# regsimple2addfp.net
KiCad netlist of a schematic drawn in EAGLE
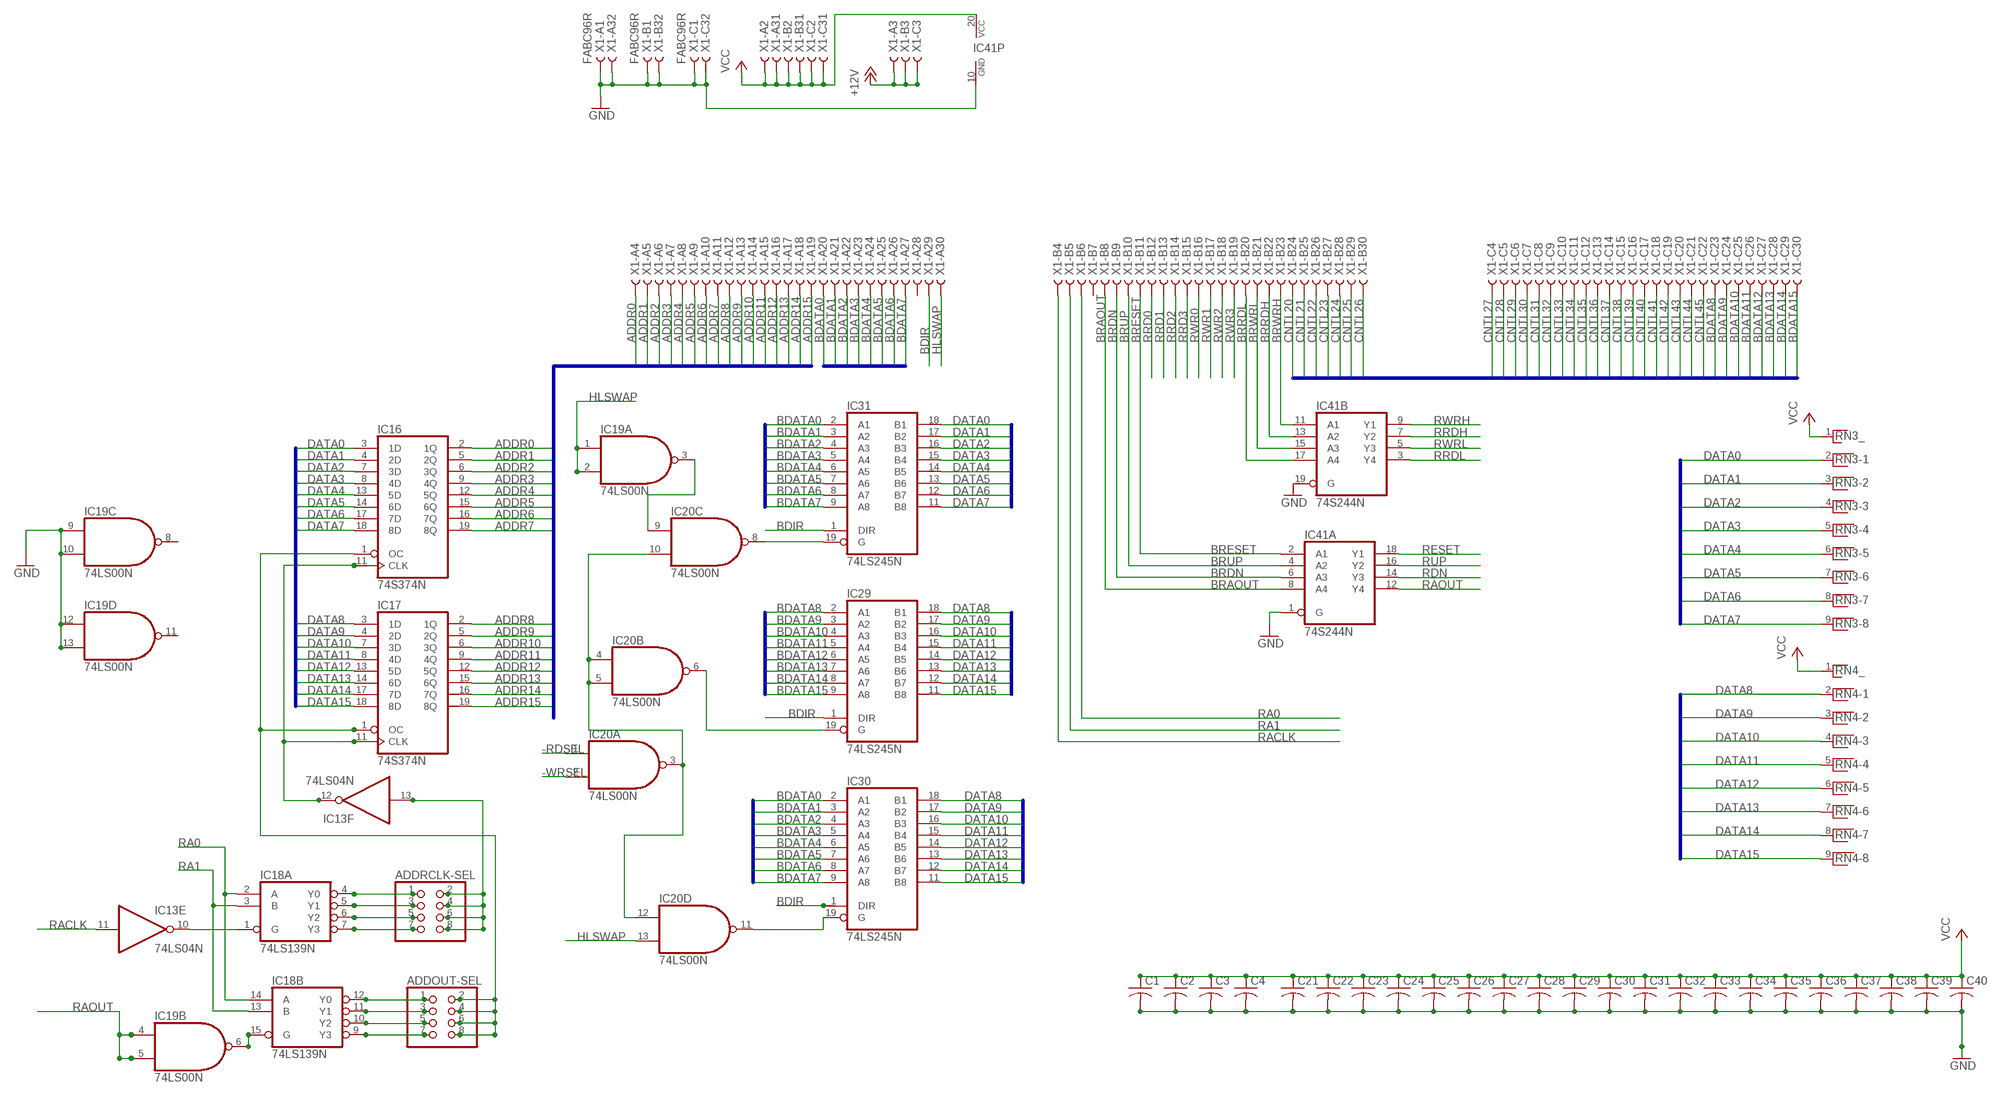
[diagram p0: schematic, sheet 1]
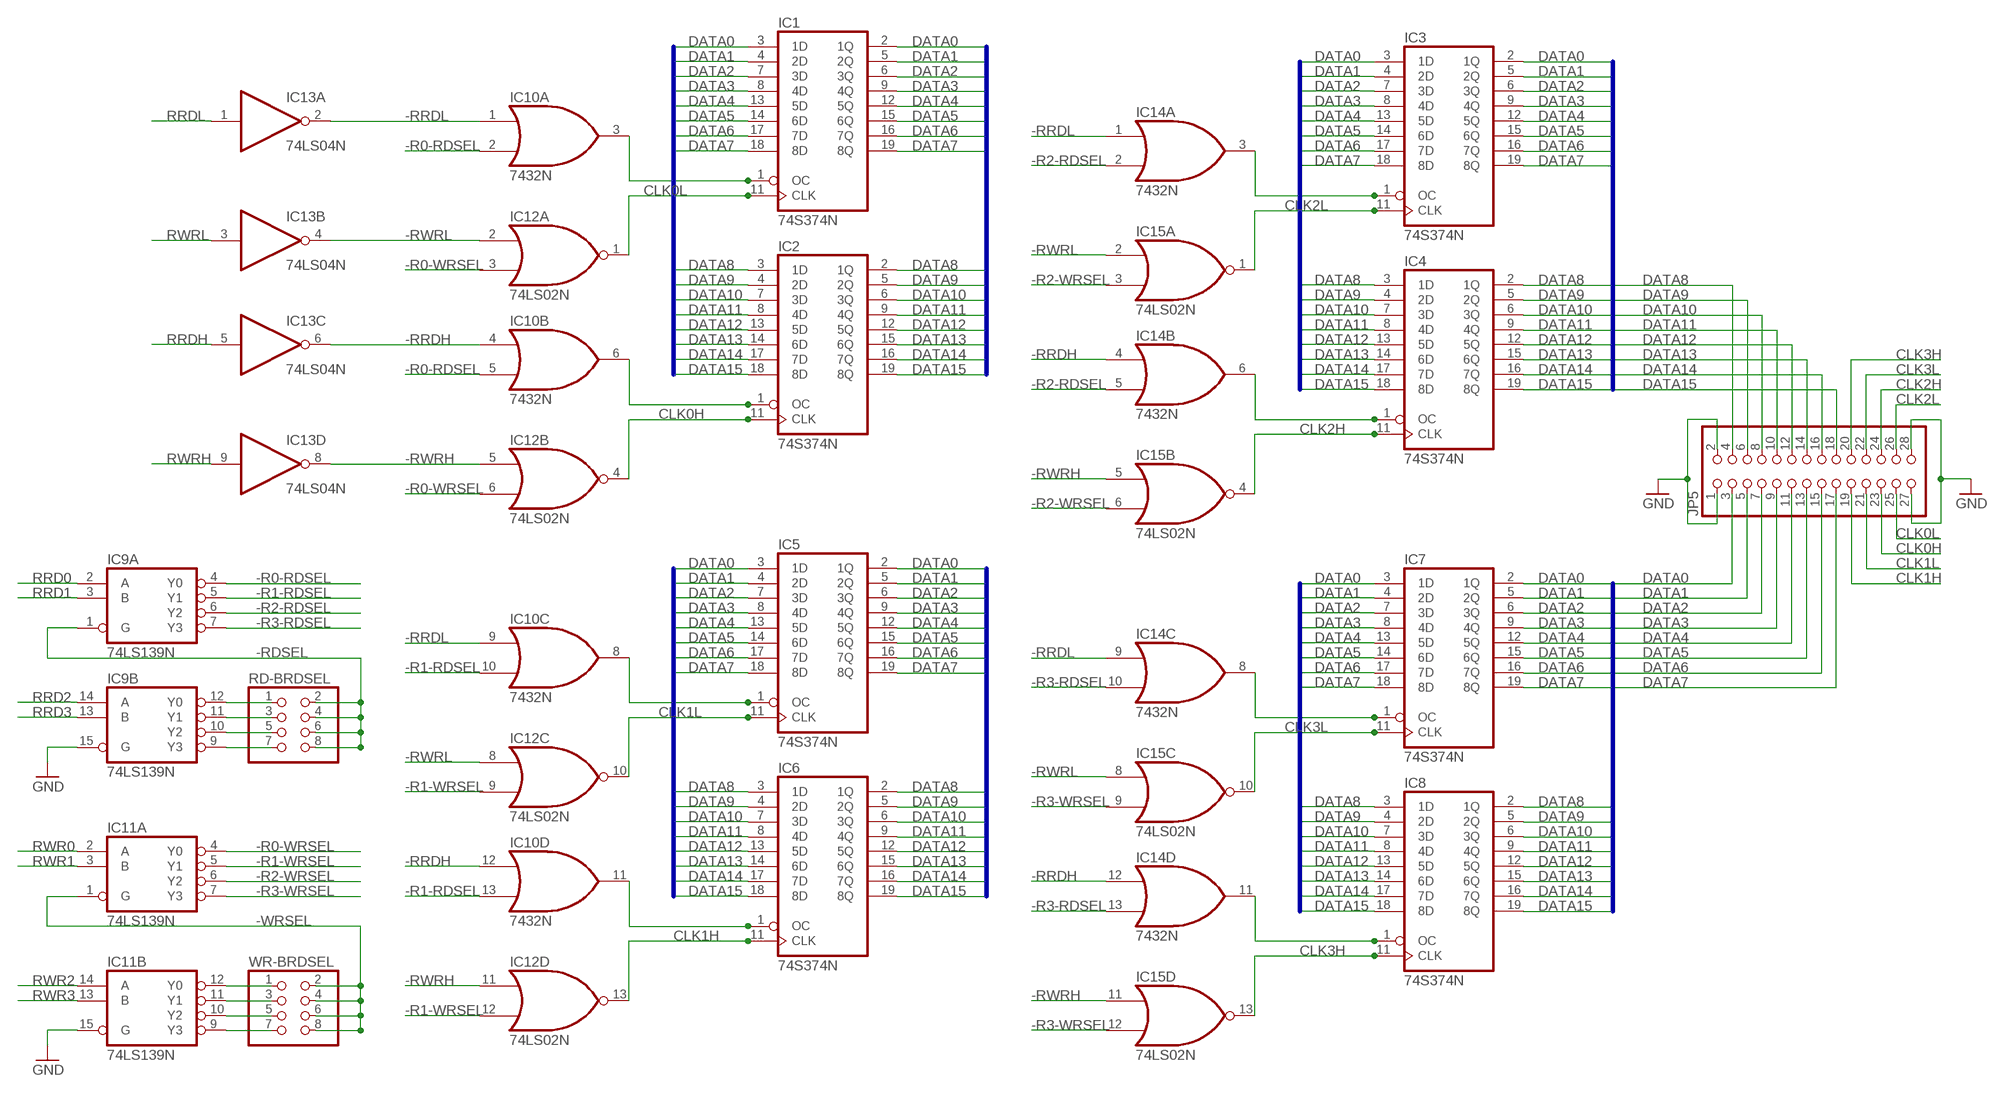
[diagram p1: schematic, sheet 2]

(export (version "E")
  (design (tool "Eeschema 10.0.6"))
  (components
    (comp (ref "IC1")
      (value "74S374N")
      (footprint "eagle-import:DIL20")
      (libsource (lib "eagle-import") (part "74374NS"))
    )
    (comp (ref "IC2")
      (value "74S374N")
      (footprint "eagle-import:DIL20")
      (libsource (lib "eagle-import") (part "74374NS"))
    )
    (comp (ref "IC3")
      (value "74S374N")
      (footprint "eagle-import:DIL20")
      (libsource (lib "eagle-import") (part "74374NS"))
    )
    (comp (ref "IC4")
      (value "74S374N")
      (footprint "eagle-import:DIL20")
      (libsource (lib "eagle-import") (part "74374NS"))
    )
    (comp (ref "IC5")
      (value "74S374N")
      (footprint "eagle-import:DIL20")
      (libsource (lib "eagle-import") (part "74374NS"))
    )
    (comp (ref "IC6")
      (value "74S374N")
      (footprint "eagle-import:DIL20")
      (libsource (lib "eagle-import") (part "74374NS"))
    )
    (comp (ref "IC7")
      (value "74S374N")
      (footprint "eagle-import:DIL20")
      (libsource (lib "eagle-import") (part "74374NS"))
    )
    (comp (ref "IC8")
      (value "74S374N")
      (footprint "eagle-import:DIL20")
      (libsource (lib "eagle-import") (part "74374NS"))
    )
    (comp (ref "IC9")
      (value "74LS139N")
      (footprint "eagle-import:DIL16")
      (libsource (lib "eagle-import") (part "74139NLS"))
    )
    (comp (ref "IC10")
      (value "7432N")
      (footprint "eagle-import:DIL14")
      (libsource (lib "eagle-import") (part "7432N"))
    )
    (comp (ref "IC11")
      (value "74LS139N")
      (footprint "eagle-import:DIL16")
      (libsource (lib "eagle-import") (part "74139NLS"))
    )
    (comp (ref "IC12")
      (value "74LS02N")
      (footprint "eagle-import:DIL14")
      (libsource (lib "eagle-import") (part "7402NLS"))
    )
    (comp (ref "IC13")
      (value "74LS04N")
      (footprint "eagle-import:DIL14")
      (libsource (lib "eagle-import") (part "7404NLS"))
    )
    (comp (ref "IC14")
      (value "7432N")
      (footprint "eagle-import:DIL14")
      (libsource (lib "eagle-import") (part "7432N"))
    )
    (comp (ref "IC15")
      (value "74LS02N")
      (footprint "eagle-import:DIL14")
      (libsource (lib "eagle-import") (part "7402NLS"))
    )
    (comp (ref "JP5")
      (value "PINHD-2X14")
      (footprint "eagle-import:2X14")
      (libsource (lib "eagle-import") (part "PINHD-2X14"))
    )
    (comp (ref "RD-BRDSEL")
      (value "PINHD-2X4")
      (footprint "eagle-import:2X04")
      (libsource (lib "eagle-import") (part "PINHD-2X4"))
    )
    (comp (ref "WR-BRDSEL")
      (value "PINHD-2X4")
      (footprint "eagle-import:2X04")
      (libsource (lib "eagle-import") (part "PINHD-2X4"))
    )
    (comp (ref "ADDOUT-SEL")
      (value "PINHD-2X4")
      (footprint "eagle-import:2X04")
      (libsource (lib "eagle-import") (part "PINHD-2X4"))
    )
    (comp (ref "ADDRCLK-SEL")
      (value "PINHD-2X4")
      (footprint "eagle-import:2X04")
      (libsource (lib "eagle-import") (part "PINHD-2X4"))
    )
    (comp (ref "C1")
      (value "C-US025-040X050")
      (footprint "eagle-import:C025-040X050")
      (libsource (lib "eagle-import") (part "C-US025-040X050"))
    )
    (comp (ref "C2")
      (value "C-US025-040X050")
      (footprint "eagle-import:C025-040X050")
      (libsource (lib "eagle-import") (part "C-US025-040X050"))
    )
    (comp (ref "C3")
      (value "C-US025-040X050")
      (footprint "eagle-import:C025-040X050")
      (libsource (lib "eagle-import") (part "C-US025-040X050"))
    )
    (comp (ref "C4")
      (value "C-US025-040X050")
      (footprint "eagle-import:C025-040X050")
      (libsource (lib "eagle-import") (part "C-US025-040X050"))
    )
    (comp (ref "C21")
      (value "C-US025-040X050")
      (footprint "eagle-import:C025-040X050")
      (libsource (lib "eagle-import") (part "C-US025-040X050"))
    )
    (comp (ref "C22")
      (value "C-US025-040X050")
      (footprint "eagle-import:C025-040X050")
      (libsource (lib "eagle-import") (part "C-US025-040X050"))
    )
    (comp (ref "C23")
      (value "C-US025-040X050")
      (footprint "eagle-import:C025-040X050")
      (libsource (lib "eagle-import") (part "C-US025-040X050"))
    )
    (comp (ref "C24")
      (value "C-US025-040X050")
      (footprint "eagle-import:C025-040X050")
      (libsource (lib "eagle-import") (part "C-US025-040X050"))
    )
    (comp (ref "C25")
      (value "C-US025-040X050")
      (footprint "eagle-import:C025-040X050")
      (libsource (lib "eagle-import") (part "C-US025-040X050"))
    )
    (comp (ref "C26")
      (value "C-US025-040X050")
      (footprint "eagle-import:C025-040X050")
      (libsource (lib "eagle-import") (part "C-US025-040X050"))
    )
    (comp (ref "C27")
      (value "C-US025-040X050")
      (footprint "eagle-import:C025-040X050")
      (libsource (lib "eagle-import") (part "C-US025-040X050"))
    )
    (comp (ref "C28")
      (value "C-US025-040X050")
      (footprint "eagle-import:C025-040X050")
      (libsource (lib "eagle-import") (part "C-US025-040X050"))
    )
    (comp (ref "C29")
      (value "C-US025-040X050")
      (footprint "eagle-import:C025-040X050")
      (libsource (lib "eagle-import") (part "C-US025-040X050"))
    )
    (comp (ref "C30")
      (value "C-US025-040X050")
      (footprint "eagle-import:C025-040X050")
      (libsource (lib "eagle-import") (part "C-US025-040X050"))
    )
    (comp (ref "C31")
      (value "C-US025-040X050")
      (footprint "eagle-import:C025-040X050")
      (libsource (lib "eagle-import") (part "C-US025-040X050"))
    )
    (comp (ref "C32")
      (value "C-US025-040X050")
      (footprint "eagle-import:C025-040X050")
      (libsource (lib "eagle-import") (part "C-US025-040X050"))
    )
    (comp (ref "C33")
      (value "C-US025-040X050")
      (footprint "eagle-import:C025-040X050")
      (libsource (lib "eagle-import") (part "C-US025-040X050"))
    )
    (comp (ref "C34")
      (value "C-US025-040X050")
      (footprint "eagle-import:C025-040X050")
      (libsource (lib "eagle-import") (part "C-US025-040X050"))
    )
    (comp (ref "C35")
      (value "C-US025-040X050")
      (footprint "eagle-import:C025-040X050")
      (libsource (lib "eagle-import") (part "C-US025-040X050"))
    )
    (comp (ref "C36")
      (value "C-US025-040X050")
      (footprint "eagle-import:C025-040X050")
      (libsource (lib "eagle-import") (part "C-US025-040X050"))
    )
    (comp (ref "C37")
      (value "C-US025-040X050")
      (footprint "eagle-import:C025-040X050")
      (libsource (lib "eagle-import") (part "C-US025-040X050"))
    )
    (comp (ref "C38")
      (value "C-US025-040X050")
      (footprint "eagle-import:C025-040X050")
      (libsource (lib "eagle-import") (part "C-US025-040X050"))
    )
    (comp (ref "C39")
      (value "C-US025-040X050")
      (footprint "eagle-import:C025-040X050")
      (libsource (lib "eagle-import") (part "C-US025-040X050"))
    )
    (comp (ref "C40")
      (value "C-US025-040X050")
      (footprint "eagle-import:C025-040X050")
      (libsource (lib "eagle-import") (part "C-US025-040X050"))
    )
    (comp (ref "IC16")
      (value "74S374N")
      (footprint "eagle-import:DIL20")
      (libsource (lib "eagle-import") (part "74374NS"))
    )
    (comp (ref "IC17")
      (value "74S374N")
      (footprint "eagle-import:DIL20")
      (libsource (lib "eagle-import") (part "74374NS"))
    )
    (comp (ref "IC18")
      (value "74LS139N")
      (footprint "eagle-import:DIL16")
      (libsource (lib "eagle-import") (part "74139NLS"))
    )
    (comp (ref "IC19")
      (value "74LS00N")
      (footprint "eagle-import:DIL14")
      (libsource (lib "eagle-import") (part "7400NLS"))
    )
    (comp (ref "IC20")
      (value "74LS00N")
      (footprint "eagle-import:DIL14")
      (libsource (lib "eagle-import") (part "7400NLS"))
    )
    (comp (ref "IC29")
      (value "74LS245N")
      (footprint "eagle-import:DIL20")
      (libsource (lib "eagle-import") (part "74245NLS"))
    )
    (comp (ref "IC30")
      (value "74LS245N")
      (footprint "eagle-import:DIL20")
      (libsource (lib "eagle-import") (part "74245NLS"))
    )
    (comp (ref "IC31")
      (value "74LS245N")
      (footprint "eagle-import:DIL20")
      (libsource (lib "eagle-import") (part "74245NLS"))
    )
    (comp (ref "IC41")
      (value "74S244N")
      (footprint "eagle-import:DIL20")
      (libsource (lib "eagle-import") (part "74244NS"))
    )
    (comp (ref "RN3")
      (value "RNX8")
      (footprint "eagle-import:RN-9")
      (libsource (lib "eagle-import") (part "RNX8"))
    )
    (comp (ref "RN4")
      (value "RNX8")
      (footprint "eagle-import:RN-9")
      (libsource (lib "eagle-import") (part "RNX8"))
    )
    (comp (ref "X1")
      (value "FABC96R")
      (footprint "eagle-import:FABC96R")
      (libsource (lib "eagle-import") (part "FABC96R"))
    )
  )
  (nets
    (net (code "1") (name "+12V") (class "Default")
      (node (ref "X1") (pin "A3") (pinfunction "B_A3") (pintype "passive"))
      (node (ref "X1") (pin "B3") (pinfunction "B_B3") (pintype "passive"))
      (node (ref "X1") (pin "C3") (pinfunction "B_C3") (pintype "passive"))
    )
    (net (code "2") (name "-R0-RDSEL") (class "Default")
      (node (ref "IC10") (pin "2") (pinfunction "I1_2") (pintype "input"))
      (node (ref "IC10") (pin "5") (pinfunction "I1_5") (pintype "input"))
      (node (ref "IC9") (pin "4") (pinfunction "Y0_4") (pintype "output"))
    )
    (net (code "3") (name "-R0-WRSEL") (class "Default")
      (node (ref "IC11") (pin "4") (pinfunction "Y0_4") (pintype "output"))
      (node (ref "IC12") (pin "3") (pinfunction "I1_3") (pintype "input"))
      (node (ref "IC12") (pin "6") (pinfunction "I1_6") (pintype "input"))
    )
    (net (code "4") (name "-R1-RDSEL") (class "Default")
      (node (ref "IC10") (pin "10") (pinfunction "I1_10") (pintype "input"))
      (node (ref "IC10") (pin "13") (pinfunction "I1_13") (pintype "input"))
      (node (ref "IC9") (pin "5") (pinfunction "Y1_5") (pintype "output"))
    )
    (net (code "5") (name "-R1-WRSEL") (class "Default")
      (node (ref "IC11") (pin "5") (pinfunction "Y1_5") (pintype "output"))
      (node (ref "IC12") (pin "12") (pinfunction "I1_12") (pintype "input"))
      (node (ref "IC12") (pin "9") (pinfunction "I1_9") (pintype "input"))
    )
    (net (code "6") (name "-R2-RDSEL") (class "Default")
      (node (ref "IC14") (pin "2") (pinfunction "I1_2") (pintype "input"))
      (node (ref "IC14") (pin "5") (pinfunction "I1_5") (pintype "input"))
      (node (ref "IC9") (pin "6") (pinfunction "Y2_6") (pintype "output"))
    )
    (net (code "7") (name "-R2-WRSEL") (class "Default")
      (node (ref "IC11") (pin "6") (pinfunction "Y2_6") (pintype "output"))
      (node (ref "IC15") (pin "3") (pinfunction "I1_3") (pintype "input"))
      (node (ref "IC15") (pin "6") (pinfunction "I1_6") (pintype "input"))
    )
    (net (code "8") (name "-R3-RDSEL") (class "Default")
      (node (ref "IC14") (pin "10") (pinfunction "I1_10") (pintype "input"))
      (node (ref "IC14") (pin "13") (pinfunction "I1_13") (pintype "input"))
      (node (ref "IC9") (pin "7") (pinfunction "Y3_7") (pintype "output"))
    )
    (net (code "9") (name "-R3-WRSEL") (class "Default")
      (node (ref "IC11") (pin "7") (pinfunction "Y3_7") (pintype "output"))
      (node (ref "IC15") (pin "12") (pinfunction "I1_12") (pintype "input"))
      (node (ref "IC15") (pin "9") (pinfunction "I1_9") (pintype "input"))
    )
    (net (code "10") (name "-RDSEL") (class "Default")
      (node (ref "IC20") (pin "1") (pinfunction "I0_1") (pintype "input"))
      (node (ref "IC9") (pin "1") (pinfunction "G_1") (pintype "input"))
      (node (ref "RD-BRDSEL") (pin "2") (pinfunction "2_2") (pintype "passive"))
      (node (ref "RD-BRDSEL") (pin "4") (pinfunction "4_4") (pintype "passive"))
      (node (ref "RD-BRDSEL") (pin "6") (pinfunction "6_6") (pintype "passive"))
      (node (ref "RD-BRDSEL") (pin "8") (pinfunction "8_8") (pintype "passive"))
    )
    (net (code "11") (name "-RRDH") (class "Default")
      (node (ref "IC10") (pin "12") (pinfunction "I0_12") (pintype "input"))
      (node (ref "IC10") (pin "4") (pinfunction "I0_4") (pintype "input"))
      (node (ref "IC13") (pin "6") (pinfunction "O_6") (pintype "output"))
      (node (ref "IC14") (pin "12") (pinfunction "I0_12") (pintype "input"))
      (node (ref "IC14") (pin "4") (pinfunction "I0_4") (pintype "input"))
    )
    (net (code "12") (name "-RRDL") (class "Default")
      (node (ref "IC10") (pin "1") (pinfunction "I0_1") (pintype "input"))
      (node (ref "IC10") (pin "9") (pinfunction "I0_9") (pintype "input"))
      (node (ref "IC13") (pin "2") (pinfunction "O_2") (pintype "output"))
      (node (ref "IC14") (pin "1") (pinfunction "I0_1") (pintype "input"))
      (node (ref "IC14") (pin "9") (pinfunction "I0_9") (pintype "input"))
    )
    (net (code "13") (name "-RWRH") (class "Default")
      (node (ref "IC12") (pin "11") (pinfunction "I0_11") (pintype "input"))
      (node (ref "IC12") (pin "5") (pinfunction "I0_5") (pintype "input"))
      (node (ref "IC13") (pin "8") (pinfunction "O_8") (pintype "output"))
      (node (ref "IC15") (pin "11") (pinfunction "I0_11") (pintype "input"))
      (node (ref "IC15") (pin "5") (pinfunction "I0_5") (pintype "input"))
    )
    (net (code "14") (name "-RWRL") (class "Default")
      (node (ref "IC12") (pin "2") (pinfunction "I0_2") (pintype "input"))
      (node (ref "IC12") (pin "8") (pinfunction "I0_8") (pintype "input"))
      (node (ref "IC13") (pin "4") (pinfunction "O_4") (pintype "output"))
      (node (ref "IC15") (pin "2") (pinfunction "I0_2") (pintype "input"))
      (node (ref "IC15") (pin "8") (pinfunction "I0_8") (pintype "input"))
    )
    (net (code "15") (name "-WRSEL") (class "Default")
      (node (ref "IC11") (pin "1") (pinfunction "G_1") (pintype "input"))
      (node (ref "IC20") (pin "2") (pinfunction "I1_2") (pintype "input"))
      (node (ref "WR-BRDSEL") (pin "2") (pinfunction "2_2") (pintype "passive"))
      (node (ref "WR-BRDSEL") (pin "4") (pinfunction "4_4") (pintype "passive"))
      (node (ref "WR-BRDSEL") (pin "6") (pinfunction "6_6") (pintype "passive"))
      (node (ref "WR-BRDSEL") (pin "8") (pinfunction "8_8") (pintype "passive"))
    )
    (net (code "16") (name "ADDR0") (class "Default")
      (node (ref "IC16") (pin "2") (pinfunction "1Q_2") (pintype "tri_state"))
      (node (ref "X1") (pin "A4") (pinfunction "B_A4") (pintype "passive"))
    )
    (net (code "17") (name "ADDR1") (class "Default")
      (node (ref "IC16") (pin "5") (pinfunction "2Q_5") (pintype "tri_state"))
      (node (ref "X1") (pin "A5") (pinfunction "B_A5") (pintype "passive"))
    )
    (net (code "18") (name "ADDR2") (class "Default")
      (node (ref "IC16") (pin "6") (pinfunction "3Q_6") (pintype "tri_state"))
      (node (ref "X1") (pin "A6") (pinfunction "B_A6") (pintype "passive"))
    )
    (net (code "19") (name "ADDR3") (class "Default")
      (node (ref "IC16") (pin "9") (pinfunction "4Q_9") (pintype "tri_state"))
      (node (ref "X1") (pin "A7") (pinfunction "B_A7") (pintype "passive"))
    )
    (net (code "20") (name "ADDR4") (class "Default")
      (node (ref "IC16") (pin "12") (pinfunction "5Q_12") (pintype "tri_state"))
      (node (ref "X1") (pin "A8") (pinfunction "B_A8") (pintype "passive"))
    )
    (net (code "21") (name "ADDR5") (class "Default")
      (node (ref "IC16") (pin "15") (pinfunction "6Q_15") (pintype "tri_state"))
      (node (ref "X1") (pin "A9") (pinfunction "B_A9") (pintype "passive"))
    )
    (net (code "22") (name "ADDR6") (class "Default")
      (node (ref "IC16") (pin "16") (pinfunction "7Q_16") (pintype "tri_state"))
      (node (ref "X1") (pin "A10") (pinfunction "B_A10") (pintype "passive"))
    )
    (net (code "23") (name "ADDR7") (class "Default")
      (node (ref "IC16") (pin "19") (pinfunction "8Q_19") (pintype "tri_state"))
      (node (ref "X1") (pin "A11") (pinfunction "B_A11") (pintype "passive"))
    )
    (net (code "24") (name "ADDR8") (class "Default")
      (node (ref "IC17") (pin "2") (pinfunction "1Q_2") (pintype "tri_state"))
      (node (ref "X1") (pin "A12") (pinfunction "B_A12") (pintype "passive"))
    )
    (net (code "25") (name "ADDR9") (class "Default")
      (node (ref "IC17") (pin "5") (pinfunction "2Q_5") (pintype "tri_state"))
      (node (ref "X1") (pin "A13") (pinfunction "B_A13") (pintype "passive"))
    )
    (net (code "26") (name "ADDR10") (class "Default")
      (node (ref "IC17") (pin "6") (pinfunction "3Q_6") (pintype "tri_state"))
      (node (ref "X1") (pin "A14") (pinfunction "B_A14") (pintype "passive"))
    )
    (net (code "27") (name "ADDR11") (class "Default")
      (node (ref "IC17") (pin "9") (pinfunction "4Q_9") (pintype "tri_state"))
      (node (ref "X1") (pin "A15") (pinfunction "B_A15") (pintype "passive"))
    )
    (net (code "28") (name "ADDR12") (class "Default")
      (node (ref "IC17") (pin "12") (pinfunction "5Q_12") (pintype "tri_state"))
      (node (ref "X1") (pin "A16") (pinfunction "B_A16") (pintype "passive"))
    )
    (net (code "29") (name "ADDR13") (class "Default")
      (node (ref "IC17") (pin "15") (pinfunction "6Q_15") (pintype "tri_state"))
      (node (ref "X1") (pin "A17") (pinfunction "B_A17") (pintype "passive"))
    )
    (net (code "30") (name "ADDR14") (class "Default")
      (node (ref "IC17") (pin "16") (pinfunction "7Q_16") (pintype "tri_state"))
      (node (ref "X1") (pin "A18") (pinfunction "B_A18") (pintype "passive"))
    )
    (net (code "31") (name "ADDR15") (class "Default")
      (node (ref "IC17") (pin "19") (pinfunction "8Q_19") (pintype "tri_state"))
      (node (ref "X1") (pin "A19") (pinfunction "B_A19") (pintype "passive"))
    )
    (net (code "32") (name "BDATA0") (class "Default")
      (node (ref "IC30") (pin "2") (pinfunction "A1_2") (pintype "bidirectional"))
      (node (ref "IC31") (pin "2") (pinfunction "A1_2") (pintype "bidirectional"))
      (node (ref "X1") (pin "A20") (pinfunction "B_A20") (pintype "passive"))
    )
    (net (code "33") (name "BDATA1") (class "Default")
      (node (ref "IC30") (pin "3") (pinfunction "A2_3") (pintype "bidirectional"))
      (node (ref "IC31") (pin "3") (pinfunction "A2_3") (pintype "bidirectional"))
      (node (ref "X1") (pin "A21") (pinfunction "B_A21") (pintype "passive"))
    )
    (net (code "34") (name "BDATA2") (class "Default")
      (node (ref "IC30") (pin "4") (pinfunction "A3_4") (pintype "bidirectional"))
      (node (ref "IC31") (pin "4") (pinfunction "A3_4") (pintype "bidirectional"))
      (node (ref "X1") (pin "A22") (pinfunction "B_A22") (pintype "passive"))
    )
    (net (code "35") (name "BDATA3") (class "Default")
      (node (ref "IC30") (pin "5") (pinfunction "A4_5") (pintype "bidirectional"))
      (node (ref "IC31") (pin "5") (pinfunction "A4_5") (pintype "bidirectional"))
      (node (ref "X1") (pin "A23") (pinfunction "B_A23") (pintype "passive"))
    )
    (net (code "36") (name "BDATA4") (class "Default")
      (node (ref "IC30") (pin "6") (pinfunction "A5_6") (pintype "bidirectional"))
      (node (ref "IC31") (pin "6") (pinfunction "A5_6") (pintype "bidirectional"))
      (node (ref "X1") (pin "A24") (pinfunction "B_A24") (pintype "passive"))
    )
    (net (code "37") (name "BDATA5") (class "Default")
      (node (ref "IC30") (pin "7") (pinfunction "A6_7") (pintype "bidirectional"))
      (node (ref "IC31") (pin "7") (pinfunction "A6_7") (pintype "bidirectional"))
      (node (ref "X1") (pin "A25") (pinfunction "B_A25") (pintype "passive"))
    )
    (net (code "38") (name "BDATA6") (class "Default")
      (node (ref "IC30") (pin "8") (pinfunction "A7_8") (pintype "bidirectional"))
      (node (ref "IC31") (pin "8") (pinfunction "A7_8") (pintype "bidirectional"))
      (node (ref "X1") (pin "A26") (pinfunction "B_A26") (pintype "passive"))
    )
    (net (code "39") (name "BDATA7") (class "Default")
      (node (ref "IC30") (pin "9") (pinfunction "A8_9") (pintype "bidirectional"))
      (node (ref "IC31") (pin "9") (pinfunction "A8_9") (pintype "bidirectional"))
      (node (ref "X1") (pin "A27") (pinfunction "B_A27") (pintype "passive"))
    )
    (net (code "40") (name "BDATA8") (class "Default")
      (node (ref "IC29") (pin "2") (pinfunction "A1_2") (pintype "bidirectional"))
      (node (ref "X1") (pin "C23") (pinfunction "B_C23") (pintype "passive"))
    )
    (net (code "41") (name "BDATA9") (class "Default")
      (node (ref "IC29") (pin "3") (pinfunction "A2_3") (pintype "bidirectional"))
      (node (ref "X1") (pin "C24") (pinfunction "B_C24") (pintype "passive"))
    )
    (net (code "42") (name "BDATA10") (class "Default")
      (node (ref "IC29") (pin "4") (pinfunction "A3_4") (pintype "bidirectional"))
      (node (ref "X1") (pin "C25") (pinfunction "B_C25") (pintype "passive"))
    )
    (net (code "43") (name "BDATA11") (class "Default")
      (node (ref "IC29") (pin "5") (pinfunction "A4_5") (pintype "bidirectional"))
      (node (ref "X1") (pin "C26") (pinfunction "B_C26") (pintype "passive"))
    )
    (net (code "44") (name "BDATA12") (class "Default")
      (node (ref "IC29") (pin "6") (pinfunction "A5_6") (pintype "bidirectional"))
      (node (ref "X1") (pin "C27") (pinfunction "B_C27") (pintype "passive"))
    )
    (net (code "45") (name "BDATA13") (class "Default")
      (node (ref "IC29") (pin "7") (pinfunction "A6_7") (pintype "bidirectional"))
      (node (ref "X1") (pin "C28") (pinfunction "B_C28") (pintype "passive"))
    )
    (net (code "46") (name "BDATA14") (class "Default")
      (node (ref "IC29") (pin "8") (pinfunction "A7_8") (pintype "bidirectional"))
      (node (ref "X1") (pin "C29") (pinfunction "B_C29") (pintype "passive"))
    )
    (net (code "47") (name "BDATA15") (class "Default")
      (node (ref "IC29") (pin "9") (pinfunction "A8_9") (pintype "bidirectional"))
      (node (ref "X1") (pin "C30") (pinfunction "B_C30") (pintype "passive"))
    )
    (net (code "48") (name "BDIR") (class "Default")
      (node (ref "IC29") (pin "1") (pinfunction "DIR_1") (pintype "input"))
      (node (ref "IC30") (pin "1") (pinfunction "DIR_1") (pintype "input"))
      (node (ref "IC31") (pin "1") (pinfunction "DIR_1") (pintype "input"))
      (node (ref "X1") (pin "A29") (pinfunction "B_A29") (pintype "passive"))
    )
    (net (code "49") (name "BRAOUT") (class "Default")
      (node (ref "IC41") (pin "8") (pinfunction "A4_8") (pintype "input"))
      (node (ref "X1") (pin "B8") (pinfunction "B_B8") (pintype "passive"))
    )
    (net (code "50") (name "BRDN") (class "Default")
      (node (ref "IC41") (pin "6") (pinfunction "A3_6") (pintype "input"))
      (node (ref "X1") (pin "B9") (pinfunction "B_B9") (pintype "passive"))
    )
    (net (code "51") (name "BRESET") (class "Default")
      (node (ref "IC41") (pin "2") (pinfunction "A1_2") (pintype "input"))
      (node (ref "X1") (pin "B11") (pinfunction "B_B11") (pintype "passive"))
    )
    (net (code "52") (name "BRRDH") (class "Default")
      (node (ref "IC41") (pin "13") (pinfunction "A2_13") (pintype "input"))
      (node (ref "X1") (pin "B22") (pinfunction "B_B22") (pintype "passive"))
    )
    (net (code "53") (name "BRRDL") (class "Default")
      (node (ref "IC41") (pin "17") (pinfunction "A4_17") (pintype "input"))
      (node (ref "X1") (pin "B20") (pinfunction "B_B20") (pintype "passive"))
    )
    (net (code "54") (name "BRUP") (class "Default")
      (node (ref "IC41") (pin "4") (pinfunction "A2_4") (pintype "input"))
      (node (ref "X1") (pin "B10") (pinfunction "B_B10") (pintype "passive"))
    )
    (net (code "55") (name "BRWRH") (class "Default")
      (node (ref "IC41") (pin "11") (pinfunction "A1_11") (pintype "input"))
      (node (ref "X1") (pin "B23") (pinfunction "B_B23") (pintype "passive"))
    )
    (net (code "56") (name "BRWRL") (class "Default")
      (node (ref "IC41") (pin "15") (pinfunction "A3_15") (pintype "input"))
      (node (ref "X1") (pin "B21") (pinfunction "B_B21") (pintype "passive"))
    )
    (net (code "57") (name "CLK0H") (class "Default")
      (node (ref "IC12") (pin "4") (pinfunction "O_4") (pintype "output"))
      (node (ref "IC2") (pin "11") (pinfunction "CLK_11") (pintype "input"))
      (node (ref "JP5") (pin "23") (pinfunction "23_23") (pintype "passive"))
    )
    (net (code "58") (name "CLK0L") (class "Default")
      (node (ref "IC1") (pin "11") (pinfunction "CLK_11") (pintype "input"))
      (node (ref "IC12") (pin "1") (pinfunction "O_1") (pintype "output"))
      (node (ref "JP5") (pin "25") (pinfunction "25_25") (pintype "passive"))
    )
    (net (code "59") (name "CLK1H") (class "Default")
      (node (ref "IC12") (pin "13") (pinfunction "O_13") (pintype "output"))
      (node (ref "IC6") (pin "11") (pinfunction "CLK_11") (pintype "input"))
      (node (ref "JP5") (pin "19") (pinfunction "19_19") (pintype "passive"))
    )
    (net (code "60") (name "CLK1L") (class "Default")
      (node (ref "IC12") (pin "10") (pinfunction "O_10") (pintype "output"))
      (node (ref "IC5") (pin "11") (pinfunction "CLK_11") (pintype "input"))
      (node (ref "JP5") (pin "21") (pinfunction "21_21") (pintype "passive"))
    )
    (net (code "61") (name "CLK2H") (class "Default")
      (node (ref "IC15") (pin "4") (pinfunction "O_4") (pintype "output"))
      (node (ref "IC4") (pin "11") (pinfunction "CLK_11") (pintype "input"))
      (node (ref "JP5") (pin "24") (pinfunction "24_24") (pintype "passive"))
    )
    (net (code "62") (name "CLK2L") (class "Default")
      (node (ref "IC15") (pin "1") (pinfunction "O_1") (pintype "output"))
      (node (ref "IC3") (pin "11") (pinfunction "CLK_11") (pintype "input"))
      (node (ref "JP5") (pin "26") (pinfunction "26_26") (pintype "passive"))
    )
    (net (code "63") (name "CLK3H") (class "Default")
      (node (ref "IC15") (pin "13") (pinfunction "O_13") (pintype "output"))
      (node (ref "IC8") (pin "11") (pinfunction "CLK_11") (pintype "input"))
      (node (ref "JP5") (pin "20") (pinfunction "20_20") (pintype "passive"))
    )
    (net (code "64") (name "CLK3L") (class "Default")
      (node (ref "IC15") (pin "10") (pinfunction "O_10") (pintype "output"))
      (node (ref "IC7") (pin "11") (pinfunction "CLK_11") (pintype "input"))
      (node (ref "JP5") (pin "22") (pinfunction "22_22") (pintype "passive"))
    )
    (net (code "65") (name "CNTL20") (class "Default")
      (node (ref "X1") (pin "B24") (pinfunction "B_B24") (pintype "passive"))
    )
    (net (code "66") (name "CNTL21") (class "Default")
      (node (ref "X1") (pin "B25") (pinfunction "B_B25") (pintype "passive"))
    )
    (net (code "67") (name "CNTL22") (class "Default")
      (node (ref "X1") (pin "B26") (pinfunction "B_B26") (pintype "passive"))
    )
    (net (code "68") (name "CNTL23") (class "Default")
      (node (ref "X1") (pin "B27") (pinfunction "B_B27") (pintype "passive"))
    )
    (net (code "69") (name "CNTL24") (class "Default")
      (node (ref "X1") (pin "B28") (pinfunction "B_B28") (pintype "passive"))
    )
    (net (code "70") (name "CNTL25") (class "Default")
      (node (ref "X1") (pin "B29") (pinfunction "B_B29") (pintype "passive"))
    )
    (net (code "71") (name "CNTL26") (class "Default")
      (node (ref "X1") (pin "B30") (pinfunction "B_B30") (pintype "passive"))
    )
    (net (code "72") (name "CNTL27") (class "Default")
      (node (ref "X1") (pin "C4") (pinfunction "B_C4") (pintype "passive"))
    )
    (net (code "73") (name "CNTL28") (class "Default")
      (node (ref "X1") (pin "C5") (pinfunction "B_C5") (pintype "passive"))
    )
    (net (code "74") (name "CNTL29") (class "Default")
      (node (ref "X1") (pin "C6") (pinfunction "B_C6") (pintype "passive"))
    )
    (net (code "75") (name "CNTL30") (class "Default")
      (node (ref "X1") (pin "C7") (pinfunction "B_C7") (pintype "passive"))
    )
    (net (code "76") (name "CNTL31") (class "Default")
      (node (ref "X1") (pin "C8") (pinfunction "B_C8") (pintype "passive"))
    )
    (net (code "77") (name "CNTL32") (class "Default")
      (node (ref "X1") (pin "C9") (pinfunction "B_C9") (pintype "passive"))
    )
    (net (code "78") (name "CNTL33") (class "Default")
      (node (ref "X1") (pin "C10") (pinfunction "B_C10") (pintype "passive"))
    )
    (net (code "79") (name "CNTL34") (class "Default")
      (node (ref "X1") (pin "C11") (pinfunction "B_C11") (pintype "passive"))
    )
    (net (code "80") (name "CNTL35") (class "Default")
      (node (ref "X1") (pin "C12") (pinfunction "B_C12") (pintype "passive"))
    )
    (net (code "81") (name "CNTL36") (class "Default")
      (node (ref "X1") (pin "C13") (pinfunction "B_C13") (pintype "passive"))
    )
    (net (code "82") (name "CNTL37") (class "Default")
      (node (ref "X1") (pin "C14") (pinfunction "B_C14") (pintype "passive"))
    )
    (net (code "83") (name "CNTL38") (class "Default")
      (node (ref "X1") (pin "C15") (pinfunction "B_C15") (pintype "passive"))
    )
    (net (code "84") (name "CNTL39") (class "Default")
      (node (ref "X1") (pin "C16") (pinfunction "B_C16") (pintype "passive"))
    )
    (net (code "85") (name "CNTL40") (class "Default")
      (node (ref "X1") (pin "C17") (pinfunction "B_C17") (pintype "passive"))
    )
    (net (code "86") (name "CNTL41") (class "Default")
      (node (ref "X1") (pin "C18") (pinfunction "B_C18") (pintype "passive"))
    )
    (net (code "87") (name "CNTL42") (class "Default")
      (node (ref "X1") (pin "C19") (pinfunction "B_C19") (pintype "passive"))
    )
    (net (code "88") (name "CNTL43") (class "Default")
      (node (ref "X1") (pin "C20") (pinfunction "B_C20") (pintype "passive"))
    )
    (net (code "89") (name "CNTL44") (class "Default")
      (node (ref "X1") (pin "C21") (pinfunction "B_C21") (pintype "passive"))
    )
    (net (code "90") (name "CNTL45") (class "Default")
      (node (ref "X1") (pin "C22") (pinfunction "B_C22") (pintype "passive"))
    )
    (net (code "91") (name "DATA0") (class "Default")
      (node (ref "IC1") (pin "2") (pinfunction "1Q_2") (pintype "tri_state"))
      (node (ref "IC1") (pin "3") (pinfunction "1D_3") (pintype "input"))
      (node (ref "IC16") (pin "3") (pinfunction "1D_3") (pintype "input"))
      (node (ref "IC3") (pin "2") (pinfunction "1Q_2") (pintype "tri_state"))
      (node (ref "IC3") (pin "3") (pinfunction "1D_3") (pintype "input"))
      (node (ref "IC31") (pin "18") (pinfunction "B1_18") (pintype "bidirectional"))
      (node (ref "IC5") (pin "2") (pinfunction "1Q_2") (pintype "tri_state"))
      (node (ref "IC5") (pin "3") (pinfunction "1D_3") (pintype "input"))
      (node (ref "IC7") (pin "2") (pinfunction "1Q_2") (pintype "tri_state"))
      (node (ref "IC7") (pin "3") (pinfunction "1D_3") (pintype "input"))
      (node (ref "JP5") (pin "3") (pinfunction "3_3") (pintype "passive"))
      (node (ref "RN3") (pin "2") (pinfunction "1_2") (pintype "passive"))
    )
    (net (code "92") (name "DATA1") (class "Default")
      (node (ref "IC1") (pin "4") (pinfunction "2D_4") (pintype "input"))
      (node (ref "IC1") (pin "5") (pinfunction "2Q_5") (pintype "tri_state"))
      (node (ref "IC16") (pin "4") (pinfunction "2D_4") (pintype "input"))
      (node (ref "IC3") (pin "4") (pinfunction "2D_4") (pintype "input"))
      (node (ref "IC3") (pin "5") (pinfunction "2Q_5") (pintype "tri_state"))
      (node (ref "IC31") (pin "17") (pinfunction "B2_17") (pintype "bidirectional"))
      (node (ref "IC5") (pin "4") (pinfunction "2D_4") (pintype "input"))
      (node (ref "IC5") (pin "5") (pinfunction "2Q_5") (pintype "tri_state"))
      (node (ref "IC7") (pin "4") (pinfunction "2D_4") (pintype "input"))
      (node (ref "IC7") (pin "5") (pinfunction "2Q_5") (pintype "tri_state"))
      (node (ref "JP5") (pin "5") (pinfunction "5_5") (pintype "passive"))
      (node (ref "RN3") (pin "3") (pinfunction "1_3") (pintype "passive"))
    )
    (net (code "93") (name "DATA2") (class "Default")
      (node (ref "IC1") (pin "6") (pinfunction "3Q_6") (pintype "tri_state"))
      (node (ref "IC1") (pin "7") (pinfunction "3D_7") (pintype "input"))
      (node (ref "IC16") (pin "7") (pinfunction "3D_7") (pintype "input"))
      (node (ref "IC3") (pin "6") (pinfunction "3Q_6") (pintype "tri_state"))
      (node (ref "IC3") (pin "7") (pinfunction "3D_7") (pintype "input"))
      (node (ref "IC31") (pin "16") (pinfunction "B3_16") (pintype "bidirectional"))
      (node (ref "IC5") (pin "6") (pinfunction "3Q_6") (pintype "tri_state"))
      (node (ref "IC5") (pin "7") (pinfunction "3D_7") (pintype "input"))
      (node (ref "IC7") (pin "6") (pinfunction "3Q_6") (pintype "tri_state"))
      (node (ref "IC7") (pin "7") (pinfunction "3D_7") (pintype "input"))
      (node (ref "JP5") (pin "7") (pinfunction "7_7") (pintype "passive"))
      (node (ref "RN3") (pin "4") (pinfunction "1_4") (pintype "passive"))
    )
    (net (code "94") (name "DATA3") (class "Default")
      (node (ref "IC1") (pin "8") (pinfunction "4D_8") (pintype "input"))
      (node (ref "IC1") (pin "9") (pinfunction "4Q_9") (pintype "tri_state"))
      (node (ref "IC16") (pin "8") (pinfunction "4D_8") (pintype "input"))
      (node (ref "IC3") (pin "8") (pinfunction "4D_8") (pintype "input"))
      (node (ref "IC3") (pin "9") (pinfunction "4Q_9") (pintype "tri_state"))
      (node (ref "IC31") (pin "15") (pinfunction "B4_15") (pintype "bidirectional"))
      (node (ref "IC5") (pin "8") (pinfunction "4D_8") (pintype "input"))
      (node (ref "IC5") (pin "9") (pinfunction "4Q_9") (pintype "tri_state"))
      (node (ref "IC7") (pin "8") (pinfunction "4D_8") (pintype "input"))
      (node (ref "IC7") (pin "9") (pinfunction "4Q_9") (pintype "tri_state"))
      (node (ref "JP5") (pin "9") (pinfunction "9_9") (pintype "passive"))
      (node (ref "RN3") (pin "5") (pinfunction "1_5") (pintype "passive"))
    )
    (net (code "95") (name "DATA4") (class "Default")
      (node (ref "IC1") (pin "12") (pinfunction "5Q_12") (pintype "tri_state"))
      (node (ref "IC1") (pin "13") (pinfunction "5D_13") (pintype "input"))
      (node (ref "IC16") (pin "13") (pinfunction "5D_13") (pintype "input"))
      (node (ref "IC3") (pin "12") (pinfunction "5Q_12") (pintype "tri_state"))
      (node (ref "IC3") (pin "13") (pinfunction "5D_13") (pintype "input"))
      (node (ref "IC31") (pin "14") (pinfunction "B5_14") (pintype "bidirectional"))
      (node (ref "IC5") (pin "12") (pinfunction "5Q_12") (pintype "tri_state"))
      (node (ref "IC5") (pin "13") (pinfunction "5D_13") (pintype "input"))
      (node (ref "IC7") (pin "12") (pinfunction "5Q_12") (pintype "tri_state"))
      (node (ref "IC7") (pin "13") (pinfunction "5D_13") (pintype "input"))
      (node (ref "JP5") (pin "11") (pinfunction "11_11") (pintype "passive"))
      (node (ref "RN3") (pin "6") (pinfunction "1_6") (pintype "passive"))
    )
    (net (code "96") (name "DATA5") (class "Default")
      (node (ref "IC1") (pin "14") (pinfunction "6D_14") (pintype "input"))
      (node (ref "IC1") (pin "15") (pinfunction "6Q_15") (pintype "tri_state"))
      (node (ref "IC16") (pin "14") (pinfunction "6D_14") (pintype "input"))
      (node (ref "IC3") (pin "14") (pinfunction "6D_14") (pintype "input"))
      (node (ref "IC3") (pin "15") (pinfunction "6Q_15") (pintype "tri_state"))
      (node (ref "IC31") (pin "13") (pinfunction "B6_13") (pintype "bidirectional"))
      (node (ref "IC5") (pin "14") (pinfunction "6D_14") (pintype "input"))
      (node (ref "IC5") (pin "15") (pinfunction "6Q_15") (pintype "tri_state"))
      (node (ref "IC7") (pin "14") (pinfunction "6D_14") (pintype "input"))
      (node (ref "IC7") (pin "15") (pinfunction "6Q_15") (pintype "tri_state"))
      (node (ref "JP5") (pin "13") (pinfunction "13_13") (pintype "passive"))
      (node (ref "RN3") (pin "7") (pinfunction "1_7") (pintype "passive"))
    )
    (net (code "97") (name "DATA6") (class "Default")
      (node (ref "IC1") (pin "16") (pinfunction "7Q_16") (pintype "tri_state"))
      (node (ref "IC1") (pin "17") (pinfunction "7D_17") (pintype "input"))
      (node (ref "IC16") (pin "17") (pinfunction "7D_17") (pintype "input"))
      (node (ref "IC3") (pin "16") (pinfunction "7Q_16") (pintype "tri_state"))
      (node (ref "IC3") (pin "17") (pinfunction "7D_17") (pintype "input"))
      (node (ref "IC31") (pin "12") (pinfunction "B7_12") (pintype "bidirectional"))
      (node (ref "IC5") (pin "16") (pinfunction "7Q_16") (pintype "tri_state"))
      (node (ref "IC5") (pin "17") (pinfunction "7D_17") (pintype "input"))
      (node (ref "IC7") (pin "16") (pinfunction "7Q_16") (pintype "tri_state"))
      (node (ref "IC7") (pin "17") (pinfunction "7D_17") (pintype "input"))
      (node (ref "JP5") (pin "15") (pinfunction "15_15") (pintype "passive"))
      (node (ref "RN3") (pin "8") (pinfunction "1_8") (pintype "passive"))
    )
    (net (code "98") (name "DATA7") (class "Default")
      (node (ref "IC1") (pin "18") (pinfunction "8D_18") (pintype "input"))
      (node (ref "IC1") (pin "19") (pinfunction "8Q_19") (pintype "tri_state"))
      (node (ref "IC16") (pin "18") (pinfunction "8D_18") (pintype "input"))
      (node (ref "IC3") (pin "18") (pinfunction "8D_18") (pintype "input"))
      (node (ref "IC3") (pin "19") (pinfunction "8Q_19") (pintype "tri_state"))
      (node (ref "IC31") (pin "11") (pinfunction "B8_11") (pintype "bidirectional"))
      (node (ref "IC5") (pin "18") (pinfunction "8D_18") (pintype "input"))
      (node (ref "IC5") (pin "19") (pinfunction "8Q_19") (pintype "tri_state"))
      (node (ref "IC7") (pin "18") (pinfunction "8D_18") (pintype "input"))
      (node (ref "IC7") (pin "19") (pinfunction "8Q_19") (pintype "tri_state"))
      (node (ref "JP5") (pin "17") (pinfunction "17_17") (pintype "passive"))
      (node (ref "RN3") (pin "9") (pinfunction "1_9") (pintype "passive"))
    )
    (net (code "99") (name "DATA8") (class "Default")
      (node (ref "IC17") (pin "3") (pinfunction "1D_3") (pintype "input"))
      (node (ref "IC2") (pin "2") (pinfunction "1Q_2") (pintype "tri_state"))
      (node (ref "IC2") (pin "3") (pinfunction "1D_3") (pintype "input"))
      (node (ref "IC29") (pin "18") (pinfunction "B1_18") (pintype "bidirectional"))
      (node (ref "IC30") (pin "18") (pinfunction "B1_18") (pintype "bidirectional"))
      (node (ref "IC4") (pin "2") (pinfunction "1Q_2") (pintype "tri_state"))
      (node (ref "IC4") (pin "3") (pinfunction "1D_3") (pintype "input"))
      (node (ref "IC6") (pin "2") (pinfunction "1Q_2") (pintype "tri_state"))
      (node (ref "IC6") (pin "3") (pinfunction "1D_3") (pintype "input"))
      (node (ref "IC8") (pin "2") (pinfunction "1Q_2") (pintype "tri_state"))
      (node (ref "IC8") (pin "3") (pinfunction "1D_3") (pintype "input"))
      (node (ref "JP5") (pin "4") (pinfunction "4_4") (pintype "passive"))
      (node (ref "RN4") (pin "2") (pinfunction "1_2") (pintype "passive"))
    )
    (net (code "100") (name "DATA9") (class "Default")
      (node (ref "IC17") (pin "4") (pinfunction "2D_4") (pintype "input"))
      (node (ref "IC2") (pin "4") (pinfunction "2D_4") (pintype "input"))
      (node (ref "IC2") (pin "5") (pinfunction "2Q_5") (pintype "tri_state"))
      (node (ref "IC29") (pin "17") (pinfunction "B2_17") (pintype "bidirectional"))
      (node (ref "IC30") (pin "17") (pinfunction "B2_17") (pintype "bidirectional"))
      (node (ref "IC4") (pin "4") (pinfunction "2D_4") (pintype "input"))
      (node (ref "IC4") (pin "5") (pinfunction "2Q_5") (pintype "tri_state"))
      (node (ref "IC6") (pin "4") (pinfunction "2D_4") (pintype "input"))
      (node (ref "IC6") (pin "5") (pinfunction "2Q_5") (pintype "tri_state"))
      (node (ref "IC8") (pin "4") (pinfunction "2D_4") (pintype "input"))
      (node (ref "IC8") (pin "5") (pinfunction "2Q_5") (pintype "tri_state"))
      (node (ref "JP5") (pin "6") (pinfunction "6_6") (pintype "passive"))
      (node (ref "RN4") (pin "3") (pinfunction "1_3") (pintype "passive"))
    )
    (net (code "101") (name "DATA10") (class "Default")
      (node (ref "IC17") (pin "7") (pinfunction "3D_7") (pintype "input"))
      (node (ref "IC2") (pin "6") (pinfunction "3Q_6") (pintype "tri_state"))
      (node (ref "IC2") (pin "7") (pinfunction "3D_7") (pintype "input"))
      (node (ref "IC29") (pin "16") (pinfunction "B3_16") (pintype "bidirectional"))
      (node (ref "IC30") (pin "16") (pinfunction "B3_16") (pintype "bidirectional"))
      (node (ref "IC4") (pin "6") (pinfunction "3Q_6") (pintype "tri_state"))
      (node (ref "IC4") (pin "7") (pinfunction "3D_7") (pintype "input"))
      (node (ref "IC6") (pin "6") (pinfunction "3Q_6") (pintype "tri_state"))
      (node (ref "IC6") (pin "7") (pinfunction "3D_7") (pintype "input"))
      (node (ref "IC8") (pin "6") (pinfunction "3Q_6") (pintype "tri_state"))
      (node (ref "IC8") (pin "7") (pinfunction "3D_7") (pintype "input"))
      (node (ref "JP5") (pin "8") (pinfunction "8_8") (pintype "passive"))
      (node (ref "RN4") (pin "4") (pinfunction "1_4") (pintype "passive"))
    )
    (net (code "102") (name "DATA11") (class "Default")
      (node (ref "IC17") (pin "8") (pinfunction "4D_8") (pintype "input"))
      (node (ref "IC2") (pin "8") (pinfunction "4D_8") (pintype "input"))
      (node (ref "IC2") (pin "9") (pinfunction "4Q_9") (pintype "tri_state"))
      (node (ref "IC29") (pin "15") (pinfunction "B4_15") (pintype "bidirectional"))
      (node (ref "IC30") (pin "15") (pinfunction "B4_15") (pintype "bidirectional"))
      (node (ref "IC4") (pin "8") (pinfunction "4D_8") (pintype "input"))
      (node (ref "IC4") (pin "9") (pinfunction "4Q_9") (pintype "tri_state"))
      (node (ref "IC6") (pin "8") (pinfunction "4D_8") (pintype "input"))
      (node (ref "IC6") (pin "9") (pinfunction "4Q_9") (pintype "tri_state"))
      (node (ref "IC8") (pin "8") (pinfunction "4D_8") (pintype "input"))
      (node (ref "IC8") (pin "9") (pinfunction "4Q_9") (pintype "tri_state"))
      (node (ref "JP5") (pin "10") (pinfunction "10_10") (pintype "passive"))
      (node (ref "RN4") (pin "5") (pinfunction "1_5") (pintype "passive"))
    )
    (net (code "103") (name "DATA12") (class "Default")
      (node (ref "IC17") (pin "13") (pinfunction "5D_13") (pintype "input"))
      (node (ref "IC2") (pin "12") (pinfunction "5Q_12") (pintype "tri_state"))
      (node (ref "IC2") (pin "13") (pinfunction "5D_13") (pintype "input"))
      (node (ref "IC29") (pin "14") (pinfunction "B5_14") (pintype "bidirectional"))
      (node (ref "IC30") (pin "14") (pinfunction "B5_14") (pintype "bidirectional"))
      (node (ref "IC4") (pin "12") (pinfunction "5Q_12") (pintype "tri_state"))
      (node (ref "IC4") (pin "13") (pinfunction "5D_13") (pintype "input"))
      (node (ref "IC6") (pin "12") (pinfunction "5Q_12") (pintype "tri_state"))
      (node (ref "IC6") (pin "13") (pinfunction "5D_13") (pintype "input"))
      (node (ref "IC8") (pin "12") (pinfunction "5Q_12") (pintype "tri_state"))
      (node (ref "IC8") (pin "13") (pinfunction "5D_13") (pintype "input"))
      (node (ref "JP5") (pin "12") (pinfunction "12_12") (pintype "passive"))
      (node (ref "RN4") (pin "6") (pinfunction "1_6") (pintype "passive"))
    )
    (net (code "104") (name "DATA13") (class "Default")
      (node (ref "IC17") (pin "14") (pinfunction "6D_14") (pintype "input"))
      (node (ref "IC2") (pin "14") (pinfunction "6D_14") (pintype "input"))
      (node (ref "IC2") (pin "15") (pinfunction "6Q_15") (pintype "tri_state"))
      (node (ref "IC29") (pin "13") (pinfunction "B6_13") (pintype "bidirectional"))
      (node (ref "IC30") (pin "13") (pinfunction "B6_13") (pintype "bidirectional"))
      (node (ref "IC4") (pin "14") (pinfunction "6D_14") (pintype "input"))
      (node (ref "IC4") (pin "15") (pinfunction "6Q_15") (pintype "tri_state"))
      (node (ref "IC6") (pin "14") (pinfunction "6D_14") (pintype "input"))
      (node (ref "IC6") (pin "15") (pinfunction "6Q_15") (pintype "tri_state"))
      (node (ref "IC8") (pin "14") (pinfunction "6D_14") (pintype "input"))
      (node (ref "IC8") (pin "15") (pinfunction "6Q_15") (pintype "tri_state"))
      (node (ref "JP5") (pin "14") (pinfunction "14_14") (pintype "passive"))
      (node (ref "RN4") (pin "7") (pinfunction "1_7") (pintype "passive"))
    )
    (net (code "105") (name "DATA14") (class "Default")
      (node (ref "IC17") (pin "17") (pinfunction "7D_17") (pintype "input"))
      (node (ref "IC2") (pin "16") (pinfunction "7Q_16") (pintype "tri_state"))
      (node (ref "IC2") (pin "17") (pinfunction "7D_17") (pintype "input"))
      (node (ref "IC29") (pin "12") (pinfunction "B7_12") (pintype "bidirectional"))
      (node (ref "IC30") (pin "12") (pinfunction "B7_12") (pintype "bidirectional"))
      (node (ref "IC4") (pin "16") (pinfunction "7Q_16") (pintype "tri_state"))
      (node (ref "IC4") (pin "17") (pinfunction "7D_17") (pintype "input"))
      (node (ref "IC6") (pin "16") (pinfunction "7Q_16") (pintype "tri_state"))
      (node (ref "IC6") (pin "17") (pinfunction "7D_17") (pintype "input"))
      (node (ref "IC8") (pin "16") (pinfunction "7Q_16") (pintype "tri_state"))
      (node (ref "IC8") (pin "17") (pinfunction "7D_17") (pintype "input"))
      (node (ref "JP5") (pin "16") (pinfunction "16_16") (pintype "passive"))
      (node (ref "RN4") (pin "8") (pinfunction "1_8") (pintype "passive"))
    )
    (net (code "106") (name "DATA15") (class "Default")
      (node (ref "IC17") (pin "18") (pinfunction "8D_18") (pintype "input"))
      (node (ref "IC2") (pin "18") (pinfunction "8D_18") (pintype "input"))
      (node (ref "IC2") (pin "19") (pinfunction "8Q_19") (pintype "tri_state"))
      (node (ref "IC29") (pin "11") (pinfunction "B8_11") (pintype "bidirectional"))
      (node (ref "IC30") (pin "11") (pinfunction "B8_11") (pintype "bidirectional"))
      (node (ref "IC4") (pin "18") (pinfunction "8D_18") (pintype "input"))
      (node (ref "IC4") (pin "19") (pinfunction "8Q_19") (pintype "tri_state"))
      (node (ref "IC6") (pin "18") (pinfunction "8D_18") (pintype "input"))
      (node (ref "IC6") (pin "19") (pinfunction "8Q_19") (pintype "tri_state"))
      (node (ref "IC8") (pin "18") (pinfunction "8D_18") (pintype "input"))
      (node (ref "IC8") (pin "19") (pinfunction "8Q_19") (pintype "tri_state"))
      (node (ref "JP5") (pin "18") (pinfunction "18_18") (pintype "passive"))
      (node (ref "RN4") (pin "9") (pinfunction "1_9") (pintype "passive"))
    )
    (net (code "107") (name "GND") (class "Default")
      (node (ref "C1") (pin "2") (pinfunction "2_2") (pintype "passive"))
      (node (ref "C2") (pin "2") (pinfunction "2_2") (pintype "passive"))
      (node (ref "C21") (pin "2") (pinfunction "2_2") (pintype "passive"))
      (node (ref "C22") (pin "2") (pinfunction "2_2") (pintype "passive"))
      (node (ref "C23") (pin "2") (pinfunction "2_2") (pintype "passive"))
      (node (ref "C24") (pin "2") (pinfunction "2_2") (pintype "passive"))
      (node (ref "C25") (pin "2") (pinfunction "2_2") (pintype "passive"))
      (node (ref "C26") (pin "2") (pinfunction "2_2") (pintype "passive"))
      (node (ref "C27") (pin "2") (pinfunction "2_2") (pintype "passive"))
      (node (ref "C28") (pin "2") (pinfunction "2_2") (pintype "passive"))
      (node (ref "C29") (pin "2") (pinfunction "2_2") (pintype "passive"))
      (node (ref "C3") (pin "2") (pinfunction "2_2") (pintype "passive"))
      (node (ref "C30") (pin "2") (pinfunction "2_2") (pintype "passive"))
      (node (ref "C31") (pin "2") (pinfunction "2_2") (pintype "passive"))
      (node (ref "C32") (pin "2") (pinfunction "2_2") (pintype "passive"))
      (node (ref "C33") (pin "2") (pinfunction "2_2") (pintype "passive"))
      (node (ref "C34") (pin "2") (pinfunction "2_2") (pintype "passive"))
      (node (ref "C35") (pin "2") (pinfunction "2_2") (pintype "passive"))
      (node (ref "C36") (pin "2") (pinfunction "2_2") (pintype "passive"))
      (node (ref "C37") (pin "2") (pinfunction "2_2") (pintype "passive"))
      (node (ref "C38") (pin "2") (pinfunction "2_2") (pintype "passive"))
      (node (ref "C39") (pin "2") (pinfunction "2_2") (pintype "passive"))
      (node (ref "C4") (pin "2") (pinfunction "2_2") (pintype "passive"))
      (node (ref "C40") (pin "2") (pinfunction "2_2") (pintype "passive"))
      (node (ref "IC11") (pin "15") (pinfunction "G_15") (pintype "input"))
      (node (ref "IC19") (pin "10") (pinfunction "I1_10") (pintype "input"))
      (node (ref "IC19") (pin "12") (pinfunction "I0_12") (pintype "input"))
      (node (ref "IC19") (pin "13") (pinfunction "I1_13") (pintype "input"))
      (node (ref "IC19") (pin "9") (pinfunction "I0_9") (pintype "input"))
      (node (ref "IC41") (pin "1") (pinfunction "G_1") (pintype "input"))
      (node (ref "IC41") (pin "10") (pinfunction "GND_10") (pintype "power_in"))
      (node (ref "IC41") (pin "19") (pinfunction "G_19") (pintype "input"))
      (node (ref "IC9") (pin "15") (pinfunction "G_15") (pintype "input"))
      (node (ref "JP5") (pin "1") (pinfunction "1_1") (pintype "passive"))
      (node (ref "JP5") (pin "2") (pinfunction "2_2") (pintype "passive"))
      (node (ref "JP5") (pin "27") (pinfunction "27_27") (pintype "passive"))
      (node (ref "JP5") (pin "28") (pinfunction "28_28") (pintype "passive"))
      (node (ref "X1") (pin "A1") (pinfunction "B_A1") (pintype "passive"))
      (node (ref "X1") (pin "A32") (pinfunction "B_A32") (pintype "passive"))
      (node (ref "X1") (pin "B1") (pinfunction "B_B1") (pintype "passive"))
      (node (ref "X1") (pin "B32") (pinfunction "B_B32") (pintype "passive"))
      (node (ref "X1") (pin "C1") (pinfunction "B_C1") (pintype "passive"))
      (node (ref "X1") (pin "C32") (pinfunction "B_C32") (pintype "passive"))
    )
    (net (code "108") (name "HLSWAP") (class "Default")
      (node (ref "IC19") (pin "1") (pinfunction "I0_1") (pintype "input"))
      (node (ref "IC19") (pin "2") (pinfunction "I1_2") (pintype "input"))
      (node (ref "IC20") (pin "13") (pinfunction "I1_13") (pintype "input"))
      (node (ref "X1") (pin "A30") (pinfunction "B_A30") (pintype "passive"))
    )
    (net (code "109") (name "Net-(IC9B-Y0)") (class "Default")
      (node (ref "IC9") (pin "12") (pinfunction "Y0_12") (pintype "output"))
      (node (ref "RD-BRDSEL") (pin "1") (pinfunction "1_1") (pintype "passive"))
    )
    (net (code "110") (name "Net-(IC9B-Y1)") (class "Default")
      (node (ref "IC9") (pin "11") (pinfunction "Y1_11") (pintype "output"))
      (node (ref "RD-BRDSEL") (pin "3") (pinfunction "3_3") (pintype "passive"))
    )
    (net (code "111") (name "Net-(IC9B-Y2)") (class "Default")
      (node (ref "IC9") (pin "10") (pinfunction "Y2_10") (pintype "output"))
      (node (ref "RD-BRDSEL") (pin "5") (pinfunction "5_5") (pintype "passive"))
    )
    (net (code "112") (name "Net-(IC9B-Y3)") (class "Default")
      (node (ref "IC9") (pin "9") (pinfunction "Y3_9") (pintype "output"))
      (node (ref "RD-BRDSEL") (pin "7") (pinfunction "7_7") (pintype "passive"))
    )
    (net (code "113") (name "Net-(IC10A-O)") (class "Default")
      (node (ref "IC1") (pin "1") (pinfunction "OC_1") (pintype "input"))
      (node (ref "IC10") (pin "3") (pinfunction "O_3") (pintype "output"))
    )
    (net (code "114") (name "Net-(IC10B-O)") (class "Default")
      (node (ref "IC10") (pin "6") (pinfunction "O_6") (pintype "output"))
      (node (ref "IC2") (pin "1") (pinfunction "OC_1") (pintype "input"))
    )
    (net (code "115") (name "Net-(IC10C-O)") (class "Default")
      (node (ref "IC10") (pin "8") (pinfunction "O_8") (pintype "output"))
      (node (ref "IC5") (pin "1") (pinfunction "OC_1") (pintype "input"))
    )
    (net (code "116") (name "Net-(IC10D-O)") (class "Default")
      (node (ref "IC10") (pin "11") (pinfunction "O_11") (pintype "output"))
      (node (ref "IC6") (pin "1") (pinfunction "OC_1") (pintype "input"))
    )
    (net (code "117") (name "Net-(IC11B-Y0)") (class "Default")
      (node (ref "IC11") (pin "12") (pinfunction "Y0_12") (pintype "output"))
      (node (ref "WR-BRDSEL") (pin "1") (pinfunction "1_1") (pintype "passive"))
    )
    (net (code "118") (name "Net-(IC11B-Y1)") (class "Default")
      (node (ref "IC11") (pin "11") (pinfunction "Y1_11") (pintype "output"))
      (node (ref "WR-BRDSEL") (pin "3") (pinfunction "3_3") (pintype "passive"))
    )
    (net (code "119") (name "Net-(IC11B-Y2)") (class "Default")
      (node (ref "IC11") (pin "10") (pinfunction "Y2_10") (pintype "output"))
      (node (ref "WR-BRDSEL") (pin "5") (pinfunction "5_5") (pintype "passive"))
    )
    (net (code "120") (name "Net-(IC11B-Y3)") (class "Default")
      (node (ref "IC11") (pin "9") (pinfunction "Y3_9") (pintype "output"))
      (node (ref "WR-BRDSEL") (pin "7") (pinfunction "7_7") (pintype "passive"))
    )
    (net (code "121") (name "Net-(IC13E-O)") (class "Default")
      (node (ref "IC13") (pin "10") (pinfunction "O_10") (pintype "output"))
      (node (ref "IC18") (pin "1") (pinfunction "G_1") (pintype "input"))
    )
    (net (code "122") (name "Net-(IC13F-I)") (class "Default")
      (node (ref "ADDRCLK-SEL") (pin "2") (pinfunction "2_2") (pintype "passive"))
      (node (ref "ADDRCLK-SEL") (pin "4") (pinfunction "4_4") (pintype "passive"))
      (node (ref "ADDRCLK-SEL") (pin "6") (pinfunction "6_6") (pintype "passive"))
      (node (ref "ADDRCLK-SEL") (pin "8") (pinfunction "8_8") (pintype "passive"))
      (node (ref "IC13") (pin "13") (pinfunction "I_13") (pintype "input"))
    )
    (net (code "123") (name "Net-(IC13F-O)") (class "Default")
      (node (ref "IC13") (pin "12") (pinfunction "O_12") (pintype "output"))
      (node (ref "IC16") (pin "11") (pinfunction "CLK_11") (pintype "input"))
      (node (ref "IC17") (pin "11") (pinfunction "CLK_11") (pintype "input"))
    )
    (net (code "124") (name "Net-(IC14A-O)") (class "Default")
      (node (ref "IC14") (pin "3") (pinfunction "O_3") (pintype "output"))
      (node (ref "IC3") (pin "1") (pinfunction "OC_1") (pintype "input"))
    )
    (net (code "125") (name "Net-(IC14B-O)") (class "Default")
      (node (ref "IC14") (pin "6") (pinfunction "O_6") (pintype "output"))
      (node (ref "IC4") (pin "1") (pinfunction "OC_1") (pintype "input"))
    )
    (net (code "126") (name "Net-(IC14C-O)") (class "Default")
      (node (ref "IC14") (pin "8") (pinfunction "O_8") (pintype "output"))
      (node (ref "IC7") (pin "1") (pinfunction "OC_1") (pintype "input"))
    )
    (net (code "127") (name "Net-(IC14D-O)") (class "Default")
      (node (ref "IC14") (pin "11") (pinfunction "O_11") (pintype "output"))
      (node (ref "IC8") (pin "1") (pinfunction "OC_1") (pintype "input"))
    )
    (net (code "128") (name "Net-(IC16A-OC)") (class "Default")
      (node (ref "ADDOUT-SEL") (pin "2") (pinfunction "2_2") (pintype "passive"))
      (node (ref "ADDOUT-SEL") (pin "4") (pinfunction "4_4") (pintype "passive"))
      (node (ref "ADDOUT-SEL") (pin "6") (pinfunction "6_6") (pintype "passive"))
      (node (ref "ADDOUT-SEL") (pin "8") (pinfunction "8_8") (pintype "passive"))
      (node (ref "IC16") (pin "1") (pinfunction "OC_1") (pintype "input"))
      (node (ref "IC17") (pin "1") (pinfunction "OC_1") (pintype "input"))
    )
    (net (code "129") (name "Net-(IC18A-Y0)") (class "Default")
      (node (ref "ADDRCLK-SEL") (pin "1") (pinfunction "1_1") (pintype "passive"))
      (node (ref "IC18") (pin "4") (pinfunction "Y0_4") (pintype "output"))
    )
    (net (code "130") (name "Net-(IC18A-Y1)") (class "Default")
      (node (ref "ADDRCLK-SEL") (pin "3") (pinfunction "3_3") (pintype "passive"))
      (node (ref "IC18") (pin "5") (pinfunction "Y1_5") (pintype "output"))
    )
    (net (code "131") (name "Net-(IC18A-Y2)") (class "Default")
      (node (ref "ADDRCLK-SEL") (pin "5") (pinfunction "5_5") (pintype "passive"))
      (node (ref "IC18") (pin "6") (pinfunction "Y2_6") (pintype "output"))
    )
    (net (code "132") (name "Net-(IC18A-Y3)") (class "Default")
      (node (ref "ADDRCLK-SEL") (pin "7") (pinfunction "7_7") (pintype "passive"))
      (node (ref "IC18") (pin "7") (pinfunction "Y3_7") (pintype "output"))
    )
    (net (code "133") (name "Net-(IC18B-G)") (class "Default")
      (node (ref "IC18") (pin "15") (pinfunction "G_15") (pintype "input"))
      (node (ref "IC19") (pin "6") (pinfunction "O_6") (pintype "output"))
    )
    (net (code "134") (name "Net-(IC18B-Y0)") (class "Default")
      (node (ref "ADDOUT-SEL") (pin "1") (pinfunction "1_1") (pintype "passive"))
      (node (ref "IC18") (pin "12") (pinfunction "Y0_12") (pintype "output"))
    )
    (net (code "135") (name "Net-(IC18B-Y1)") (class "Default")
      (node (ref "ADDOUT-SEL") (pin "3") (pinfunction "3_3") (pintype "passive"))
      (node (ref "IC18") (pin "11") (pinfunction "Y1_11") (pintype "output"))
    )
    (net (code "136") (name "Net-(IC18B-Y2)") (class "Default")
      (node (ref "ADDOUT-SEL") (pin "5") (pinfunction "5_5") (pintype "passive"))
      (node (ref "IC18") (pin "10") (pinfunction "Y2_10") (pintype "output"))
    )
    (net (code "137") (name "Net-(IC18B-Y3)") (class "Default")
      (node (ref "ADDOUT-SEL") (pin "7") (pinfunction "7_7") (pintype "passive"))
      (node (ref "IC18") (pin "9") (pinfunction "Y3_9") (pintype "output"))
    )
    (net (code "138") (name "Net-(IC19A-O)") (class "Default")
      (node (ref "IC19") (pin "3") (pinfunction "O_3") (pintype "output"))
      (node (ref "IC20") (pin "9") (pinfunction "I0_9") (pintype "input"))
    )
    (net (code "139") (name "Net-(IC20A-O)") (class "Default")
      (node (ref "IC20") (pin "10") (pinfunction "I1_10") (pintype "input"))
      (node (ref "IC20") (pin "12") (pinfunction "I0_12") (pintype "input"))
      (node (ref "IC20") (pin "3") (pinfunction "O_3") (pintype "output"))
      (node (ref "IC20") (pin "4") (pinfunction "I0_4") (pintype "input"))
      (node (ref "IC20") (pin "5") (pinfunction "I1_5") (pintype "input"))
    )
    (net (code "140") (name "Net-(IC20B-O)") (class "Default")
      (node (ref "IC20") (pin "6") (pinfunction "O_6") (pintype "output"))
      (node (ref "IC29") (pin "19") (pinfunction "G_19") (pintype "input"))
    )
    (net (code "141") (name "Net-(IC20C-O)") (class "Default")
      (node (ref "IC20") (pin "8") (pinfunction "O_8") (pintype "output"))
      (node (ref "IC31") (pin "19") (pinfunction "G_19") (pintype "input"))
    )
    (net (code "142") (name "Net-(IC20D-O)") (class "Default")
      (node (ref "IC20") (pin "11") (pinfunction "O_11") (pintype "output"))
      (node (ref "IC30") (pin "19") (pinfunction "G_19") (pintype "input"))
    )
    (net (code "143") (name "RA0") (class "Default")
      (node (ref "IC18") (pin "14") (pinfunction "A_14") (pintype "input"))
      (node (ref "IC18") (pin "2") (pinfunction "A_2") (pintype "input"))
      (node (ref "X1") (pin "B6") (pinfunction "B_B6") (pintype "passive"))
    )
    (net (code "144") (name "RA1") (class "Default")
      (node (ref "IC18") (pin "13") (pinfunction "B_13") (pintype "input"))
      (node (ref "IC18") (pin "3") (pinfunction "B_3") (pintype "input"))
      (node (ref "X1") (pin "B5") (pinfunction "B_B5") (pintype "passive"))
    )
    (net (code "145") (name "RACLK") (class "Default")
      (node (ref "IC13") (pin "11") (pinfunction "I_11") (pintype "input"))
      (node (ref "X1") (pin "B4") (pinfunction "B_B4") (pintype "passive"))
    )
    (net (code "146") (name "RAOUT") (class "Default")
      (node (ref "IC19") (pin "4") (pinfunction "I0_4") (pintype "input"))
      (node (ref "IC19") (pin "5") (pinfunction "I1_5") (pintype "input"))
      (node (ref "IC41") (pin "12") (pinfunction "Y4_12") (pintype "tri_state"))
    )
    (net (code "147") (name "RDN") (class "Default")
      (node (ref "IC41") (pin "14") (pinfunction "Y3_14") (pintype "tri_state"))
    )
    (net (code "148") (name "RESET") (class "Default")
      (node (ref "IC41") (pin "18") (pinfunction "Y1_18") (pintype "tri_state"))
    )
    (net (code "149") (name "RRD0") (class "Default")
      (node (ref "IC9") (pin "2") (pinfunction "A_2") (pintype "input"))
      (node (ref "X1") (pin "B12") (pinfunction "B_B12") (pintype "passive"))
    )
    (net (code "150") (name "RRD1") (class "Default")
      (node (ref "IC9") (pin "3") (pinfunction "B_3") (pintype "input"))
      (node (ref "X1") (pin "B13") (pinfunction "B_B13") (pintype "passive"))
    )
    (net (code "151") (name "RRD2") (class "Default")
      (node (ref "IC9") (pin "14") (pinfunction "A_14") (pintype "input"))
      (node (ref "X1") (pin "B14") (pinfunction "B_B14") (pintype "passive"))
    )
    (net (code "152") (name "RRD3") (class "Default")
      (node (ref "IC9") (pin "13") (pinfunction "B_13") (pintype "input"))
      (node (ref "X1") (pin "B15") (pinfunction "B_B15") (pintype "passive"))
    )
    (net (code "153") (name "RRDH") (class "Default")
      (node (ref "IC13") (pin "5") (pinfunction "I_5") (pintype "input"))
      (node (ref "IC41") (pin "7") (pinfunction "Y2_7") (pintype "tri_state"))
    )
    (net (code "154") (name "RRDL") (class "Default")
      (node (ref "IC13") (pin "1") (pinfunction "I_1") (pintype "input"))
      (node (ref "IC41") (pin "3") (pinfunction "Y4_3") (pintype "tri_state"))
    )
    (net (code "155") (name "RUP") (class "Default")
      (node (ref "IC41") (pin "16") (pinfunction "Y2_16") (pintype "tri_state"))
    )
    (net (code "156") (name "RWR0") (class "Default")
      (node (ref "IC11") (pin "2") (pinfunction "A_2") (pintype "input"))
      (node (ref "X1") (pin "B16") (pinfunction "B_B16") (pintype "passive"))
    )
    (net (code "157") (name "RWR1") (class "Default")
      (node (ref "IC11") (pin "3") (pinfunction "B_3") (pintype "input"))
      (node (ref "X1") (pin "B17") (pinfunction "B_B17") (pintype "passive"))
    )
    (net (code "158") (name "RWR2") (class "Default")
      (node (ref "IC11") (pin "14") (pinfunction "A_14") (pintype "input"))
      (node (ref "X1") (pin "B18") (pinfunction "B_B18") (pintype "passive"))
    )
    (net (code "159") (name "RWR3") (class "Default")
      (node (ref "IC11") (pin "13") (pinfunction "B_13") (pintype "input"))
      (node (ref "X1") (pin "B19") (pinfunction "B_B19") (pintype "passive"))
    )
    (net (code "160") (name "RWRH") (class "Default")
      (node (ref "IC13") (pin "9") (pinfunction "I_9") (pintype "input"))
      (node (ref "IC41") (pin "9") (pinfunction "Y1_9") (pintype "tri_state"))
    )
    (net (code "161") (name "RWRL") (class "Default")
      (node (ref "IC13") (pin "3") (pinfunction "I_3") (pintype "input"))
      (node (ref "IC41") (pin "5") (pinfunction "Y3_5") (pintype "tri_state"))
    )
    (net (code "162") (name "VCC") (class "Default")
      (node (ref "C1") (pin "1") (pinfunction "1_1") (pintype "passive"))
      (node (ref "C2") (pin "1") (pinfunction "1_1") (pintype "passive"))
      (node (ref "C21") (pin "1") (pinfunction "1_1") (pintype "passive"))
      (node (ref "C22") (pin "1") (pinfunction "1_1") (pintype "passive"))
      (node (ref "C23") (pin "1") (pinfunction "1_1") (pintype "passive"))
      (node (ref "C24") (pin "1") (pinfunction "1_1") (pintype "passive"))
      (node (ref "C25") (pin "1") (pinfunction "1_1") (pintype "passive"))
      (node (ref "C26") (pin "1") (pinfunction "1_1") (pintype "passive"))
      (node (ref "C27") (pin "1") (pinfunction "1_1") (pintype "passive"))
      (node (ref "C28") (pin "1") (pinfunction "1_1") (pintype "passive"))
      (node (ref "C29") (pin "1") (pinfunction "1_1") (pintype "passive"))
      (node (ref "C3") (pin "1") (pinfunction "1_1") (pintype "passive"))
      (node (ref "C30") (pin "1") (pinfunction "1_1") (pintype "passive"))
      (node (ref "C31") (pin "1") (pinfunction "1_1") (pintype "passive"))
      (node (ref "C32") (pin "1") (pinfunction "1_1") (pintype "passive"))
      (node (ref "C33") (pin "1") (pinfunction "1_1") (pintype "passive"))
      (node (ref "C34") (pin "1") (pinfunction "1_1") (pintype "passive"))
      (node (ref "C35") (pin "1") (pinfunction "1_1") (pintype "passive"))
      (node (ref "C36") (pin "1") (pinfunction "1_1") (pintype "passive"))
      (node (ref "C37") (pin "1") (pinfunction "1_1") (pintype "passive"))
      (node (ref "C38") (pin "1") (pinfunction "1_1") (pintype "passive"))
      (node (ref "C39") (pin "1") (pinfunction "1_1") (pintype "passive"))
      (node (ref "C4") (pin "1") (pinfunction "1_1") (pintype "passive"))
      (node (ref "C40") (pin "1") (pinfunction "1_1") (pintype "passive"))
      (node (ref "IC41") (pin "20") (pinfunction "VCC_20") (pintype "power_in"))
      (node (ref "RN3") (pin "1") (pinfunction "1_1") (pintype "passive"))
      (node (ref "RN4") (pin "1") (pinfunction "1_1") (pintype "passive"))
      (node (ref "X1") (pin "A2") (pinfunction "B_A2") (pintype "passive"))
      (node (ref "X1") (pin "A31") (pinfunction "B_A31") (pintype "passive"))
      (node (ref "X1") (pin "B2") (pinfunction "B_B2") (pintype "passive"))
      (node (ref "X1") (pin "B31") (pinfunction "B_B31") (pintype "passive"))
      (node (ref "X1") (pin "C2") (pinfunction "B_C2") (pintype "passive"))
      (node (ref "X1") (pin "C31") (pinfunction "B_C31") (pintype "passive"))
    )
    (net (code "163") (name "unconnected-(IC19C-O-Pad8)") (class "Default")
      (node (ref "IC19") (pin "8") (pinfunction "O_8") (pintype "output"))
    )
    (net (code "164") (name "unconnected-(IC19D-O-Pad11)") (class "Default")
      (node (ref "IC19") (pin "11") (pinfunction "O_11") (pintype "output"))
    )
    (net (code "165") (name "unconnected-(X1BJ-B-PadB7)") (class "Default")
      (node (ref "X1") (pin "B7") (pinfunction "B_B7") (pintype "passive"))
    )
    (net (code "166") (name "unconnected-(X1U-B-PadA28)") (class "Default")
      (node (ref "X1") (pin "A28") (pinfunction "B_A28") (pintype "passive"))
    )
  )
)
